# VIC20_SExpII.net
KiCad netlist of a schematic drawn in EAGLE
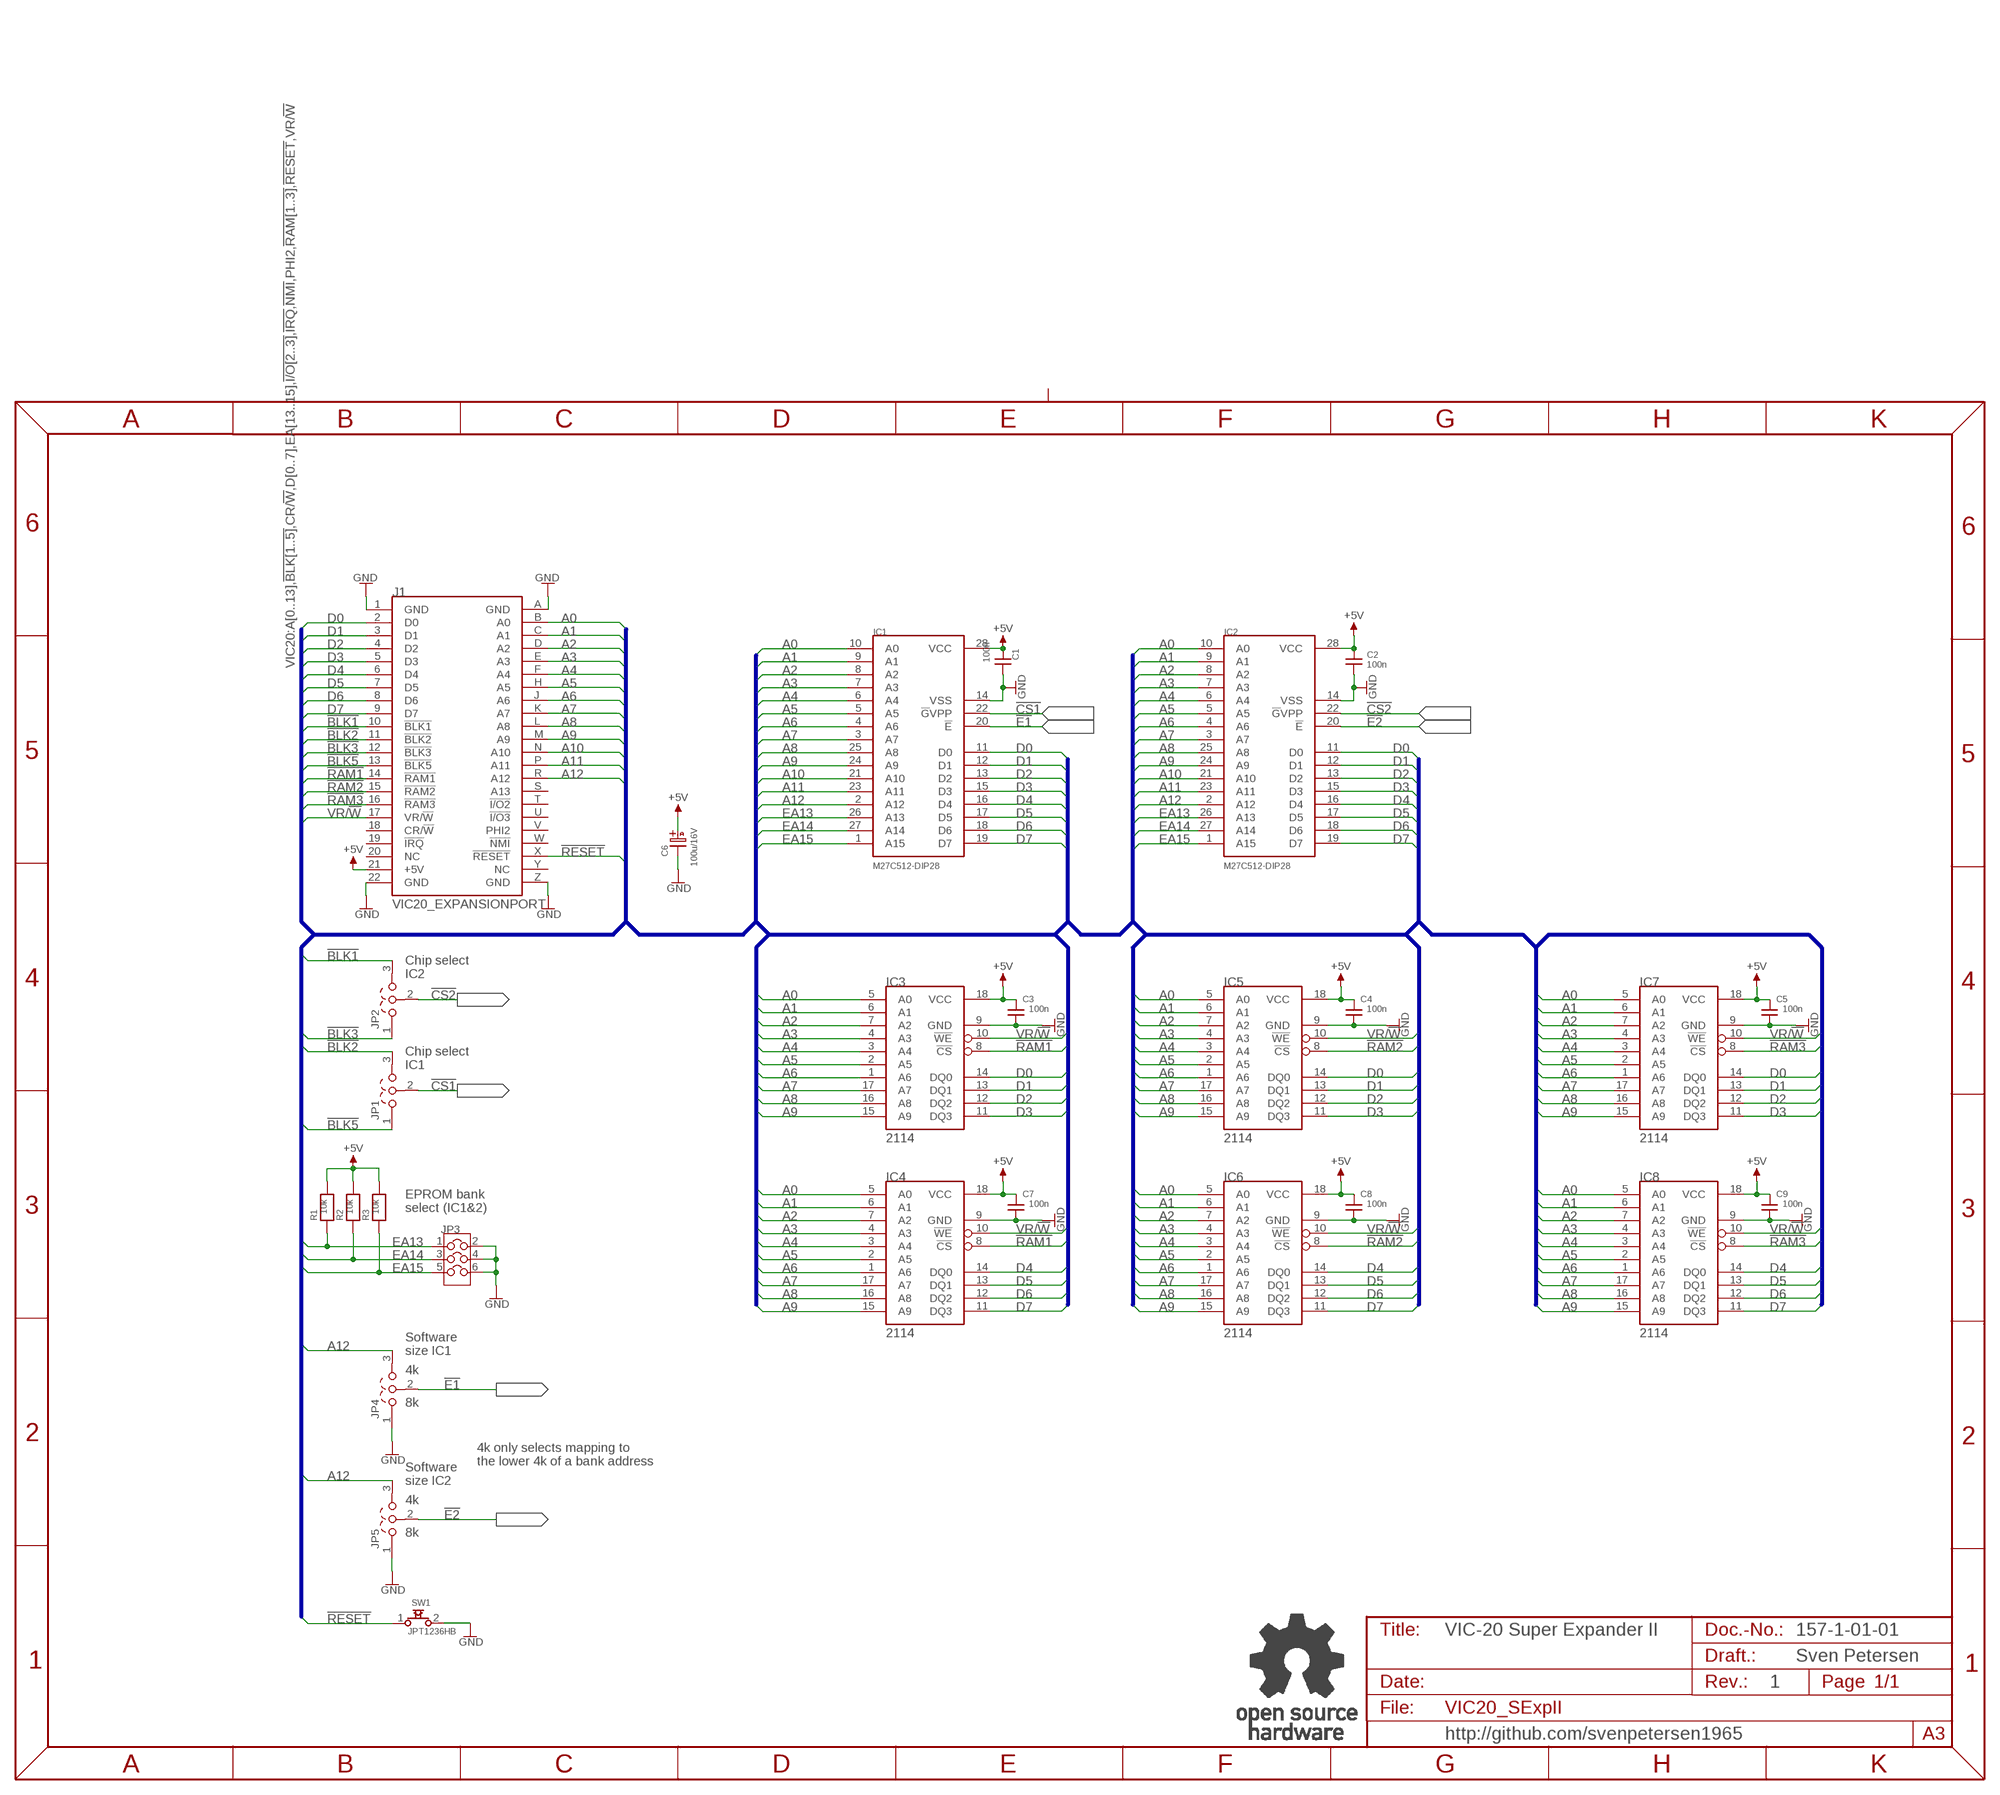
[diagram p0: schematic, sheet 1]

(export (version "E")
  (design (tool "Eeschema 10.0.6"))
  (components
    (comp (ref "C1")
      (value "100n")
      (footprint "eagle-import:C-2,5")
      (libsource (lib "eagle-import") (part "CAP01"))
    )
    (comp (ref "C2")
      (value "100n")
      (footprint "eagle-import:C-2,5")
      (libsource (lib "eagle-import") (part "CAP01"))
    )
    (comp (ref "C3")
      (value "100n")
      (footprint "eagle-import:C-2,5")
      (libsource (lib "eagle-import") (part "CAP01"))
    )
    (comp (ref "C4")
      (value "100n")
      (footprint "eagle-import:C-2,5")
      (libsource (lib "eagle-import") (part "CAP01"))
    )
    (comp (ref "C5")
      (value "100n")
      (footprint "eagle-import:C-2,5")
      (libsource (lib "eagle-import") (part "CAP01"))
    )
    (comp (ref "C6")
      (value "100u/16V")
      (footprint "eagle-import:C07_2,5")
      (libsource (lib "eagle-import") (part "C07/2,5"))
    )
    (comp (ref "C7")
      (value "100n")
      (footprint "eagle-import:C-2,5")
      (libsource (lib "eagle-import") (part "CAP01"))
    )
    (comp (ref "C8")
      (value "100n")
      (footprint "eagle-import:C-2,5")
      (libsource (lib "eagle-import") (part "CAP01"))
    )
    (comp (ref "C9")
      (value "100n")
      (footprint "eagle-import:C-2,5")
      (libsource (lib "eagle-import") (part "CAP01"))
    )
    (comp (ref "IC1")
      (value "M27C512-DIP28")
      (footprint "eagle-import:DIL28-6")
      (libsource (lib "eagle-import") (part "M27C512-DIP28"))
    )
    (comp (ref "IC2")
      (value "M27C512-DIP28")
      (footprint "eagle-import:DIL28-6")
      (libsource (lib "eagle-import") (part "M27C512-DIP28"))
    )
    (comp (ref "IC3")
      (value "2114")
      (footprint "eagle-import:DIL18")
      (libsource (lib "eagle-import") (part "2114"))
    )
    (comp (ref "IC4")
      (value "2114")
      (footprint "eagle-import:DIL18")
      (libsource (lib "eagle-import") (part "2114"))
    )
    (comp (ref "IC5")
      (value "2114")
      (footprint "eagle-import:DIL18")
      (libsource (lib "eagle-import") (part "2114"))
    )
    (comp (ref "IC6")
      (value "2114")
      (footprint "eagle-import:DIL18")
      (libsource (lib "eagle-import") (part "2114"))
    )
    (comp (ref "IC7")
      (value "2114")
      (footprint "eagle-import:DIL18")
      (libsource (lib "eagle-import") (part "2114"))
    )
    (comp (ref "IC8")
      (value "2114")
      (footprint "eagle-import:DIL18")
      (libsource (lib "eagle-import") (part "2114"))
    )
    (comp (ref "J1")
      (value "VIC20_EXPANSIONPORT")
      (footprint "eagle-import:VIC20_EXPANSION")
      (libsource (lib "eagle-import") (part "VIC20_EXPANSIONPORT"))
    )
    (comp (ref "JP1")
      (value "COMBI-3P")
      (footprint "eagle-import:COMBI-3P")
      (libsource (lib "eagle-import") (part "COMBI-3P"))
    )
    (comp (ref "JP2")
      (value "COMBI-3P")
      (footprint "eagle-import:COMBI-3P")
      (libsource (lib "eagle-import") (part "COMBI-3P"))
    )
    (comp (ref "JP3")
      (value "COMBI-3X2P")
      (footprint "eagle-import:COMBI-3X2")
      (libsource (lib "eagle-import") (part "COMBI-3X2P"))
    )
    (comp (ref "JP4")
      (value "COMBI-3P")
      (footprint "eagle-import:COMBI-3P")
      (libsource (lib "eagle-import") (part "COMBI-3P"))
    )
    (comp (ref "JP5")
      (value "COMBI-3P")
      (footprint "eagle-import:COMBI-3P")
      (libsource (lib "eagle-import") (part "COMBI-3P"))
    )
    (comp (ref "R1")
      (value "10k")
      (footprint "eagle-import:R-10")
      (libsource (lib "eagle-import") (part "RES04"))
    )
    (comp (ref "R2")
      (value "10k")
      (footprint "eagle-import:R-10")
      (libsource (lib "eagle-import") (part "RES04"))
    )
    (comp (ref "R3")
      (value "10k")
      (footprint "eagle-import:R-10")
      (libsource (lib "eagle-import") (part "RES04"))
    )
    (comp (ref "SW1")
      (value "JPT1236HB")
      (footprint "eagle-import:JTP_1236HB")
      (libsource (lib "eagle-import") (part "JPT1236HB"))
    )
    (comp (ref "U$2")
      (value "OPEN_SOURCE_HW")
      (footprint "eagle-import:OPENHW")
      (libsource (lib "eagle-import") (part "OPEN_SOURCE_HW"))
    )
  )
  (nets
    (net (code "5") (name "+5V") (class "Default")
      (node (ref "C1") (pin "1") (pinfunction "1_1") (pintype "passive"))
      (node (ref "C2") (pin "1") (pinfunction "1_1") (pintype "passive"))
      (node (ref "C3") (pin "2") (pinfunction "2_2") (pintype "passive"))
      (node (ref "C4") (pin "2") (pinfunction "2_2") (pintype "passive"))
      (node (ref "C5") (pin "2") (pinfunction "2_2") (pintype "passive"))
      (node (ref "C6") (pin "A") (pinfunction "+_A") (pintype "passive"))
      (node (ref "C7") (pin "2") (pinfunction "2_2") (pintype "passive"))
      (node (ref "C8") (pin "2") (pinfunction "2_2") (pintype "passive"))
      (node (ref "C9") (pin "2") (pinfunction "2_2") (pintype "passive"))
      (node (ref "IC1") (pin "28") (pinfunction "VCC_28") (pintype "power_in"))
      (node (ref "IC2") (pin "28") (pinfunction "VCC_28") (pintype "power_in"))
      (node (ref "IC3") (pin "18") (pinfunction "VCC_18") (pintype "power_in"))
      (node (ref "IC4") (pin "18") (pinfunction "VCC_18") (pintype "power_in"))
      (node (ref "IC5") (pin "18") (pinfunction "VCC_18") (pintype "power_in"))
      (node (ref "IC6") (pin "18") (pinfunction "VCC_18") (pintype "power_in"))
      (node (ref "IC7") (pin "18") (pinfunction "VCC_18") (pintype "power_in"))
      (node (ref "IC8") (pin "18") (pinfunction "VCC_18") (pintype "power_in"))
      (node (ref "J1") (pin "21") (pinfunction "+5V_21") (pintype "power_in"))
      (node (ref "R1") (pin "2") (pinfunction "2_2") (pintype "passive"))
      (node (ref "R2") (pin "2") (pinfunction "2_2") (pintype "passive"))
      (node (ref "R3") (pin "2") (pinfunction "2_2") (pintype "passive"))
    )
    (net (code "6") (name "/A0") (class "Default")
      (node (ref "IC1") (pin "10") (pinfunction "A0_10") (pintype "input"))
      (node (ref "IC2") (pin "10") (pinfunction "A0_10") (pintype "input"))
      (node (ref "IC3") (pin "5") (pinfunction "A0_5") (pintype "input"))
      (node (ref "IC4") (pin "5") (pinfunction "A0_5") (pintype "input"))
      (node (ref "IC5") (pin "5") (pinfunction "A0_5") (pintype "input"))
      (node (ref "IC6") (pin "5") (pinfunction "A0_5") (pintype "input"))
      (node (ref "IC7") (pin "5") (pinfunction "A0_5") (pintype "input"))
      (node (ref "IC8") (pin "5") (pinfunction "A0_5") (pintype "input"))
      (node (ref "J1") (pin "B") (pinfunction "A0_B") (pintype "bidirectional"))
    )
    (net (code "7") (name "/A1") (class "Default")
      (node (ref "IC1") (pin "9") (pinfunction "A1_9") (pintype "input"))
      (node (ref "IC2") (pin "9") (pinfunction "A1_9") (pintype "input"))
      (node (ref "IC3") (pin "6") (pinfunction "A1_6") (pintype "input"))
      (node (ref "IC4") (pin "6") (pinfunction "A1_6") (pintype "input"))
      (node (ref "IC5") (pin "6") (pinfunction "A1_6") (pintype "input"))
      (node (ref "IC6") (pin "6") (pinfunction "A1_6") (pintype "input"))
      (node (ref "IC7") (pin "6") (pinfunction "A1_6") (pintype "input"))
      (node (ref "IC8") (pin "6") (pinfunction "A1_6") (pintype "input"))
      (node (ref "J1") (pin "C") (pinfunction "A1_C") (pintype "bidirectional"))
    )
    (net (code "8") (name "/A2") (class "Default")
      (node (ref "IC1") (pin "8") (pinfunction "A2_8") (pintype "input"))
      (node (ref "IC2") (pin "8") (pinfunction "A2_8") (pintype "input"))
      (node (ref "IC3") (pin "7") (pinfunction "A2_7") (pintype "input"))
      (node (ref "IC4") (pin "7") (pinfunction "A2_7") (pintype "input"))
      (node (ref "IC5") (pin "7") (pinfunction "A2_7") (pintype "input"))
      (node (ref "IC6") (pin "7") (pinfunction "A2_7") (pintype "input"))
      (node (ref "IC7") (pin "7") (pinfunction "A2_7") (pintype "input"))
      (node (ref "IC8") (pin "7") (pinfunction "A2_7") (pintype "input"))
      (node (ref "J1") (pin "D") (pinfunction "A2_D") (pintype "bidirectional"))
    )
    (net (code "9") (name "/A3") (class "Default")
      (node (ref "IC1") (pin "7") (pinfunction "A3_7") (pintype "input"))
      (node (ref "IC2") (pin "7") (pinfunction "A3_7") (pintype "input"))
      (node (ref "IC3") (pin "4") (pinfunction "A3_4") (pintype "input"))
      (node (ref "IC4") (pin "4") (pinfunction "A3_4") (pintype "input"))
      (node (ref "IC5") (pin "4") (pinfunction "A3_4") (pintype "input"))
      (node (ref "IC6") (pin "4") (pinfunction "A3_4") (pintype "input"))
      (node (ref "IC7") (pin "4") (pinfunction "A3_4") (pintype "input"))
      (node (ref "IC8") (pin "4") (pinfunction "A3_4") (pintype "input"))
      (node (ref "J1") (pin "E") (pinfunction "A3_E") (pintype "bidirectional"))
    )
    (net (code "10") (name "/A4") (class "Default")
      (node (ref "IC1") (pin "6") (pinfunction "A4_6") (pintype "input"))
      (node (ref "IC2") (pin "6") (pinfunction "A4_6") (pintype "input"))
      (node (ref "IC3") (pin "3") (pinfunction "A4_3") (pintype "input"))
      (node (ref "IC4") (pin "3") (pinfunction "A4_3") (pintype "input"))
      (node (ref "IC5") (pin "3") (pinfunction "A4_3") (pintype "input"))
      (node (ref "IC6") (pin "3") (pinfunction "A4_3") (pintype "input"))
      (node (ref "IC7") (pin "3") (pinfunction "A4_3") (pintype "input"))
      (node (ref "IC8") (pin "3") (pinfunction "A4_3") (pintype "input"))
      (node (ref "J1") (pin "F") (pinfunction "A4_F") (pintype "bidirectional"))
    )
    (net (code "11") (name "/A5") (class "Default")
      (node (ref "IC1") (pin "5") (pinfunction "A5_5") (pintype "input"))
      (node (ref "IC2") (pin "5") (pinfunction "A5_5") (pintype "input"))
      (node (ref "IC3") (pin "2") (pinfunction "A5_2") (pintype "input"))
      (node (ref "IC4") (pin "2") (pinfunction "A5_2") (pintype "input"))
      (node (ref "IC5") (pin "2") (pinfunction "A5_2") (pintype "input"))
      (node (ref "IC6") (pin "2") (pinfunction "A5_2") (pintype "input"))
      (node (ref "IC7") (pin "2") (pinfunction "A5_2") (pintype "input"))
      (node (ref "IC8") (pin "2") (pinfunction "A5_2") (pintype "input"))
      (node (ref "J1") (pin "H") (pinfunction "A5_H") (pintype "bidirectional"))
    )
    (net (code "12") (name "/A6") (class "Default")
      (node (ref "IC1") (pin "4") (pinfunction "A6_4") (pintype "input"))
      (node (ref "IC2") (pin "4") (pinfunction "A6_4") (pintype "input"))
      (node (ref "IC3") (pin "1") (pinfunction "A6_1") (pintype "input"))
      (node (ref "IC4") (pin "1") (pinfunction "A6_1") (pintype "input"))
      (node (ref "IC5") (pin "1") (pinfunction "A6_1") (pintype "input"))
      (node (ref "IC6") (pin "1") (pinfunction "A6_1") (pintype "input"))
      (node (ref "IC7") (pin "1") (pinfunction "A6_1") (pintype "input"))
      (node (ref "IC8") (pin "1") (pinfunction "A6_1") (pintype "input"))
      (node (ref "J1") (pin "J") (pinfunction "A6_J") (pintype "bidirectional"))
    )
    (net (code "13") (name "/A7") (class "Default")
      (node (ref "IC1") (pin "3") (pinfunction "A7_3") (pintype "input"))
      (node (ref "IC2") (pin "3") (pinfunction "A7_3") (pintype "input"))
      (node (ref "IC3") (pin "17") (pinfunction "A7_17") (pintype "input"))
      (node (ref "IC4") (pin "17") (pinfunction "A7_17") (pintype "input"))
      (node (ref "IC5") (pin "17") (pinfunction "A7_17") (pintype "input"))
      (node (ref "IC6") (pin "17") (pinfunction "A7_17") (pintype "input"))
      (node (ref "IC7") (pin "17") (pinfunction "A7_17") (pintype "input"))
      (node (ref "IC8") (pin "17") (pinfunction "A7_17") (pintype "input"))
      (node (ref "J1") (pin "K") (pinfunction "A7_K") (pintype "bidirectional"))
    )
    (net (code "14") (name "/A8") (class "Default")
      (node (ref "IC1") (pin "25") (pinfunction "A8_25") (pintype "input"))
      (node (ref "IC2") (pin "25") (pinfunction "A8_25") (pintype "input"))
      (node (ref "IC3") (pin "16") (pinfunction "A8_16") (pintype "input"))
      (node (ref "IC4") (pin "16") (pinfunction "A8_16") (pintype "input"))
      (node (ref "IC5") (pin "16") (pinfunction "A8_16") (pintype "input"))
      (node (ref "IC6") (pin "16") (pinfunction "A8_16") (pintype "input"))
      (node (ref "IC7") (pin "16") (pinfunction "A8_16") (pintype "input"))
      (node (ref "IC8") (pin "16") (pinfunction "A8_16") (pintype "input"))
      (node (ref "J1") (pin "L") (pinfunction "A8_L") (pintype "bidirectional"))
    )
    (net (code "15") (name "/A9") (class "Default")
      (node (ref "IC1") (pin "24") (pinfunction "A9_24") (pintype "input"))
      (node (ref "IC2") (pin "24") (pinfunction "A9_24") (pintype "input"))
      (node (ref "IC3") (pin "15") (pinfunction "A9_15") (pintype "input"))
      (node (ref "IC4") (pin "15") (pinfunction "A9_15") (pintype "input"))
      (node (ref "IC5") (pin "15") (pinfunction "A9_15") (pintype "input"))
      (node (ref "IC6") (pin "15") (pinfunction "A9_15") (pintype "input"))
      (node (ref "IC7") (pin "15") (pinfunction "A9_15") (pintype "input"))
      (node (ref "IC8") (pin "15") (pinfunction "A9_15") (pintype "input"))
      (node (ref "J1") (pin "M") (pinfunction "A9_M") (pintype "bidirectional"))
    )
    (net (code "16") (name "/A10") (class "Default")
      (node (ref "IC1") (pin "21") (pinfunction "A10_21") (pintype "input"))
      (node (ref "IC2") (pin "21") (pinfunction "A10_21") (pintype "input"))
      (node (ref "J1") (pin "N") (pinfunction "A10_N") (pintype "bidirectional"))
    )
    (net (code "17") (name "/A11") (class "Default")
      (node (ref "IC1") (pin "23") (pinfunction "A11_23") (pintype "input"))
      (node (ref "IC2") (pin "23") (pinfunction "A11_23") (pintype "input"))
      (node (ref "J1") (pin "P") (pinfunction "A11_P") (pintype "bidirectional"))
    )
    (net (code "18") (name "/A12") (class "Default")
      (node (ref "IC1") (pin "2") (pinfunction "A12_2") (pintype "input"))
      (node (ref "IC2") (pin "2") (pinfunction "A12_2") (pintype "input"))
      (node (ref "J1") (pin "R") (pinfunction "A12_R") (pintype "bidirectional"))
      (node (ref "JP4") (pin "3") (pinfunction "3_3") (pintype "bidirectional"))
      (node (ref "JP5") (pin "3") (pinfunction "3_3") (pintype "bidirectional"))
    )
    (net (code "19") (name "/D0") (class "Default")
      (node (ref "IC1") (pin "11") (pinfunction "D0_11") (pintype "bidirectional"))
      (node (ref "IC2") (pin "11") (pinfunction "D0_11") (pintype "bidirectional"))
      (node (ref "IC3") (pin "14") (pinfunction "DQ0_14") (pintype "bidirectional"))
      (node (ref "IC5") (pin "14") (pinfunction "DQ0_14") (pintype "bidirectional"))
      (node (ref "IC7") (pin "14") (pinfunction "DQ0_14") (pintype "bidirectional"))
      (node (ref "J1") (pin "2") (pinfunction "D0_2") (pintype "bidirectional"))
    )
    (net (code "20") (name "/D1") (class "Default")
      (node (ref "IC1") (pin "12") (pinfunction "D1_12") (pintype "bidirectional"))
      (node (ref "IC2") (pin "12") (pinfunction "D1_12") (pintype "bidirectional"))
      (node (ref "IC3") (pin "13") (pinfunction "DQ1_13") (pintype "bidirectional"))
      (node (ref "IC5") (pin "13") (pinfunction "DQ1_13") (pintype "bidirectional"))
      (node (ref "IC7") (pin "13") (pinfunction "DQ1_13") (pintype "bidirectional"))
      (node (ref "J1") (pin "3") (pinfunction "D1_3") (pintype "bidirectional"))
    )
    (net (code "21") (name "/D2") (class "Default")
      (node (ref "IC1") (pin "13") (pinfunction "D2_13") (pintype "bidirectional"))
      (node (ref "IC2") (pin "13") (pinfunction "D2_13") (pintype "bidirectional"))
      (node (ref "IC3") (pin "12") (pinfunction "DQ2_12") (pintype "bidirectional"))
      (node (ref "IC5") (pin "12") (pinfunction "DQ2_12") (pintype "bidirectional"))
      (node (ref "IC7") (pin "12") (pinfunction "DQ2_12") (pintype "bidirectional"))
      (node (ref "J1") (pin "4") (pinfunction "D2_4") (pintype "bidirectional"))
    )
    (net (code "22") (name "/D3") (class "Default")
      (node (ref "IC1") (pin "15") (pinfunction "D3_15") (pintype "bidirectional"))
      (node (ref "IC2") (pin "15") (pinfunction "D3_15") (pintype "bidirectional"))
      (node (ref "IC3") (pin "11") (pinfunction "DQ3_11") (pintype "bidirectional"))
      (node (ref "IC5") (pin "11") (pinfunction "DQ3_11") (pintype "bidirectional"))
      (node (ref "IC7") (pin "11") (pinfunction "DQ3_11") (pintype "bidirectional"))
      (node (ref "J1") (pin "5") (pinfunction "D3_5") (pintype "bidirectional"))
    )
    (net (code "23") (name "/D4") (class "Default")
      (node (ref "IC1") (pin "16") (pinfunction "D4_16") (pintype "bidirectional"))
      (node (ref "IC2") (pin "16") (pinfunction "D4_16") (pintype "bidirectional"))
      (node (ref "IC4") (pin "14") (pinfunction "DQ0_14") (pintype "bidirectional"))
      (node (ref "IC6") (pin "14") (pinfunction "DQ0_14") (pintype "bidirectional"))
      (node (ref "IC8") (pin "14") (pinfunction "DQ0_14") (pintype "bidirectional"))
      (node (ref "J1") (pin "6") (pinfunction "D4_6") (pintype "bidirectional"))
    )
    (net (code "24") (name "/D5") (class "Default")
      (node (ref "IC1") (pin "17") (pinfunction "D5_17") (pintype "bidirectional"))
      (node (ref "IC2") (pin "17") (pinfunction "D5_17") (pintype "bidirectional"))
      (node (ref "IC4") (pin "13") (pinfunction "DQ1_13") (pintype "bidirectional"))
      (node (ref "IC6") (pin "13") (pinfunction "DQ1_13") (pintype "bidirectional"))
      (node (ref "IC8") (pin "13") (pinfunction "DQ1_13") (pintype "bidirectional"))
      (node (ref "J1") (pin "7") (pinfunction "D5_7") (pintype "bidirectional"))
    )
    (net (code "25") (name "/D6") (class "Default")
      (node (ref "IC1") (pin "18") (pinfunction "D6_18") (pintype "bidirectional"))
      (node (ref "IC2") (pin "18") (pinfunction "D6_18") (pintype "bidirectional"))
      (node (ref "IC4") (pin "12") (pinfunction "DQ2_12") (pintype "bidirectional"))
      (node (ref "IC6") (pin "12") (pinfunction "DQ2_12") (pintype "bidirectional"))
      (node (ref "IC8") (pin "12") (pinfunction "DQ2_12") (pintype "bidirectional"))
      (node (ref "J1") (pin "8") (pinfunction "D6_8") (pintype "bidirectional"))
    )
    (net (code "26") (name "/D7") (class "Default")
      (node (ref "IC1") (pin "19") (pinfunction "D7_19") (pintype "bidirectional"))
      (node (ref "IC2") (pin "19") (pinfunction "D7_19") (pintype "bidirectional"))
      (node (ref "IC4") (pin "11") (pinfunction "DQ3_11") (pintype "bidirectional"))
      (node (ref "IC6") (pin "11") (pinfunction "DQ3_11") (pintype "bidirectional"))
      (node (ref "IC8") (pin "11") (pinfunction "DQ3_11") (pintype "bidirectional"))
      (node (ref "J1") (pin "9") (pinfunction "D7_9") (pintype "bidirectional"))
    )
    (net (code "27") (name "/EA13") (class "Default")
      (node (ref "IC1") (pin "26") (pinfunction "A13_26") (pintype "input"))
      (node (ref "IC2") (pin "26") (pinfunction "A13_26") (pintype "input"))
      (node (ref "JP3") (pin "1") (pinfunction "1_1") (pintype "bidirectional"))
      (node (ref "R1") (pin "1") (pinfunction "1_1") (pintype "passive"))
    )
    (net (code "28") (name "/EA14") (class "Default")
      (node (ref "IC1") (pin "27") (pinfunction "A14_27") (pintype "input"))
      (node (ref "IC2") (pin "27") (pinfunction "A14_27") (pintype "input"))
      (node (ref "JP3") (pin "3") (pinfunction "3_3") (pintype "bidirectional"))
      (node (ref "R2") (pin "1") (pinfunction "1_1") (pintype "passive"))
    )
    (net (code "29") (name "/EA15") (class "Default")
      (node (ref "IC1") (pin "1") (pinfunction "A15_1") (pintype "input"))
      (node (ref "IC2") (pin "1") (pinfunction "A15_1") (pintype "input"))
      (node (ref "JP3") (pin "5") (pinfunction "5_5") (pintype "bidirectional"))
      (node (ref "R3") (pin "1") (pinfunction "1_1") (pintype "passive"))
    )
    (net (code "30") (name "/NC") (class "Default")
      (node (ref "J1") (pin "20") (pinfunction "NC_20") (pintype "power_in"))
    )
    (net (code "31") (name "/VR{slash}~{W}") (class "Default")
      (node (ref "IC3") (pin "10") (pinfunction "~{WE}_10") (pintype "input"))
      (node (ref "IC4") (pin "10") (pinfunction "~{WE}_10") (pintype "input"))
      (node (ref "IC5") (pin "10") (pinfunction "~{WE}_10") (pintype "input"))
      (node (ref "IC6") (pin "10") (pinfunction "~{WE}_10") (pintype "input"))
      (node (ref "IC7") (pin "10") (pinfunction "~{WE}_10") (pintype "input"))
      (node (ref "IC8") (pin "10") (pinfunction "~{WE}_10") (pintype "input"))
      (node (ref "J1") (pin "17") (pinfunction "VR/~{W}_17") (pintype "output"))
    )
    (net (code "33") (name "/~{BLK1}") (class "Default")
      (node (ref "J1") (pin "10") (pinfunction "~{BLK1}_10") (pintype "input"))
      (node (ref "JP2") (pin "3") (pinfunction "3_3") (pintype "bidirectional"))
    )
    (net (code "34") (name "/~{BLK2}") (class "Default")
      (node (ref "J1") (pin "11") (pinfunction "~{BLK2}_11") (pintype "input"))
      (node (ref "JP1") (pin "3") (pinfunction "3_3") (pintype "bidirectional"))
    )
    (net (code "35") (name "/~{BLK3}") (class "Default")
      (node (ref "J1") (pin "12") (pinfunction "~{BLK3}_12") (pintype "output"))
      (node (ref "JP2") (pin "1") (pinfunction "1_1") (pintype "bidirectional"))
    )
    (net (code "36") (name "/~{BLK5}") (class "Default")
      (node (ref "J1") (pin "13") (pinfunction "~{BLK5}_13") (pintype "output"))
      (node (ref "JP1") (pin "1") (pinfunction "1_1") (pintype "bidirectional"))
    )
    (net (code "37") (name "/~{CS1}") (class "Default")
      (node (ref "IC1") (pin "22") (pinfunction "~{G}VPP_22") (pintype "input"))
      (node (ref "JP1") (pin "2") (pinfunction "2_2") (pintype "bidirectional"))
    )
    (net (code "38") (name "/~{CS2}") (class "Default")
      (node (ref "IC2") (pin "22") (pinfunction "~{G}VPP_22") (pintype "input"))
      (node (ref "JP2") (pin "2") (pinfunction "2_2") (pintype "bidirectional"))
    )
    (net (code "39") (name "/~{E1}") (class "Default")
      (node (ref "IC1") (pin "20") (pinfunction "~{E}_20") (pintype "input"))
      (node (ref "JP4") (pin "2") (pinfunction "2_2") (pintype "bidirectional"))
    )
    (net (code "40") (name "/~{E2}") (class "Default")
      (node (ref "IC2") (pin "20") (pinfunction "~{E}_20") (pintype "input"))
      (node (ref "JP5") (pin "2") (pinfunction "2_2") (pintype "bidirectional"))
    )
    (net (code "41") (name "/~{RAM1}") (class "Default")
      (node (ref "IC3") (pin "8") (pinfunction "~{CS}_8") (pintype "input"))
      (node (ref "IC4") (pin "8") (pinfunction "~{CS}_8") (pintype "input"))
      (node (ref "J1") (pin "14") (pinfunction "~{RAM1}_14") (pintype "input"))
    )
    (net (code "42") (name "/~{RAM2}") (class "Default")
      (node (ref "IC5") (pin "8") (pinfunction "~{CS}_8") (pintype "input"))
      (node (ref "IC6") (pin "8") (pinfunction "~{CS}_8") (pintype "input"))
      (node (ref "J1") (pin "15") (pinfunction "~{RAM2}_15") (pintype "output"))
    )
    (net (code "43") (name "/~{RAM3}") (class "Default")
      (node (ref "IC7") (pin "8") (pinfunction "~{CS}_8") (pintype "input"))
      (node (ref "IC8") (pin "8") (pinfunction "~{CS}_8") (pintype "input"))
      (node (ref "J1") (pin "16") (pinfunction "~{RAM3}_16") (pintype "output"))
    )
    (net (code "44") (name "/~{RESET}") (class "Default")
      (node (ref "J1") (pin "X") (pinfunction "~{RESET}_X") (pintype "open_collector"))
      (node (ref "SW1") (pin "1") (pinfunction "1_1") (pintype "passive"))
    )
    (net (code "45") (name "GND") (class "Default")
      (node (ref "C1") (pin "2") (pinfunction "2_2") (pintype "passive"))
      (node (ref "C2") (pin "2") (pinfunction "2_2") (pintype "passive"))
      (node (ref "C3") (pin "1") (pinfunction "1_1") (pintype "passive"))
      (node (ref "C4") (pin "1") (pinfunction "1_1") (pintype "passive"))
      (node (ref "C5") (pin "1") (pinfunction "1_1") (pintype "passive"))
      (node (ref "C6") (pin "K") (pinfunction "-_K") (pintype "passive"))
      (node (ref "C7") (pin "1") (pinfunction "1_1") (pintype "passive"))
      (node (ref "C8") (pin "1") (pinfunction "1_1") (pintype "passive"))
      (node (ref "C9") (pin "1") (pinfunction "1_1") (pintype "passive"))
      (node (ref "IC1") (pin "14") (pinfunction "VSS_14") (pintype "power_in"))
      (node (ref "IC2") (pin "14") (pinfunction "VSS_14") (pintype "power_in"))
      (node (ref "IC3") (pin "9") (pinfunction "GND_9") (pintype "power_in"))
      (node (ref "IC4") (pin "9") (pinfunction "GND_9") (pintype "power_in"))
      (node (ref "IC5") (pin "9") (pinfunction "GND_9") (pintype "power_in"))
      (node (ref "IC6") (pin "9") (pinfunction "GND_9") (pintype "power_in"))
      (node (ref "IC7") (pin "9") (pinfunction "GND_9") (pintype "power_in"))
      (node (ref "IC8") (pin "9") (pinfunction "GND_9") (pintype "power_in"))
      (node (ref "J1") (pin "1") (pinfunction "GND_1") (pintype "power_in"))
      (node (ref "J1") (pin "22") (pinfunction "GND_22") (pintype "power_in"))
      (node (ref "J1") (pin "A") (pinfunction "GND_A") (pintype "power_in"))
      (node (ref "J1") (pin "Z") (pinfunction "GND_Z") (pintype "power_in"))
      (node (ref "JP3") (pin "2") (pinfunction "2_2") (pintype "bidirectional"))
      (node (ref "JP3") (pin "4") (pinfunction "4_4") (pintype "bidirectional"))
      (node (ref "JP3") (pin "6") (pinfunction "6_6") (pintype "bidirectional"))
      (node (ref "JP4") (pin "1") (pinfunction "1_1") (pintype "bidirectional"))
      (node (ref "JP5") (pin "1") (pinfunction "1_1") (pintype "bidirectional"))
      (node (ref "SW1") (pin "2") (pinfunction "2_2") (pintype "passive"))
    )
    (net (code "46") (name "unconnected-(J1-A13-PadS)") (class "Default")
      (node (ref "J1") (pin "S") (pinfunction "A13_S") (pintype "bidirectional"))
    )
    (net (code "47") (name "unconnected-(J1-CR{slash}~{W}-Pad18)") (class "Default")
      (node (ref "J1") (pin "18") (pinfunction "CR/~{W}_18") (pintype "output"))
    )
    (net (code "48") (name "unconnected-(J1-NC-PadY)") (class "Default")
      (node (ref "J1") (pin "Y") (pinfunction "NC_Y") (pintype "bidirectional"))
    )
    (net (code "49") (name "unconnected-(J1-PHI2-PadV)") (class "Default")
      (node (ref "J1") (pin "V") (pinfunction "PHI2_V") (pintype "bidirectional"))
    )
    (net (code "50") (name "unconnected-(J1-~{IRQ}-Pad19)") (class "Default")
      (node (ref "J1") (pin "19") (pinfunction "~{IRQ}_19") (pintype "input"))
    )
    (net (code "51") (name "unconnected-(J1-~{I{slash}O2}-PadT)") (class "Default")
      (node (ref "J1") (pin "T") (pinfunction "~{I/O2}_T") (pintype "output"))
    )
    (net (code "52") (name "unconnected-(J1-~{I{slash}O3}-PadU)") (class "Default")
      (node (ref "J1") (pin "U") (pinfunction "~{I/O3}_U") (pintype "output"))
    )
    (net (code "53") (name "unconnected-(J1-~{NMI}-PadW)") (class "Default")
      (node (ref "J1") (pin "W") (pinfunction "~{NMI}_W") (pintype "input"))
    )
  )
)
